# Project_Hail_Fally.net
KiCad netlist of a schematic drawn in EasyEDA Pro
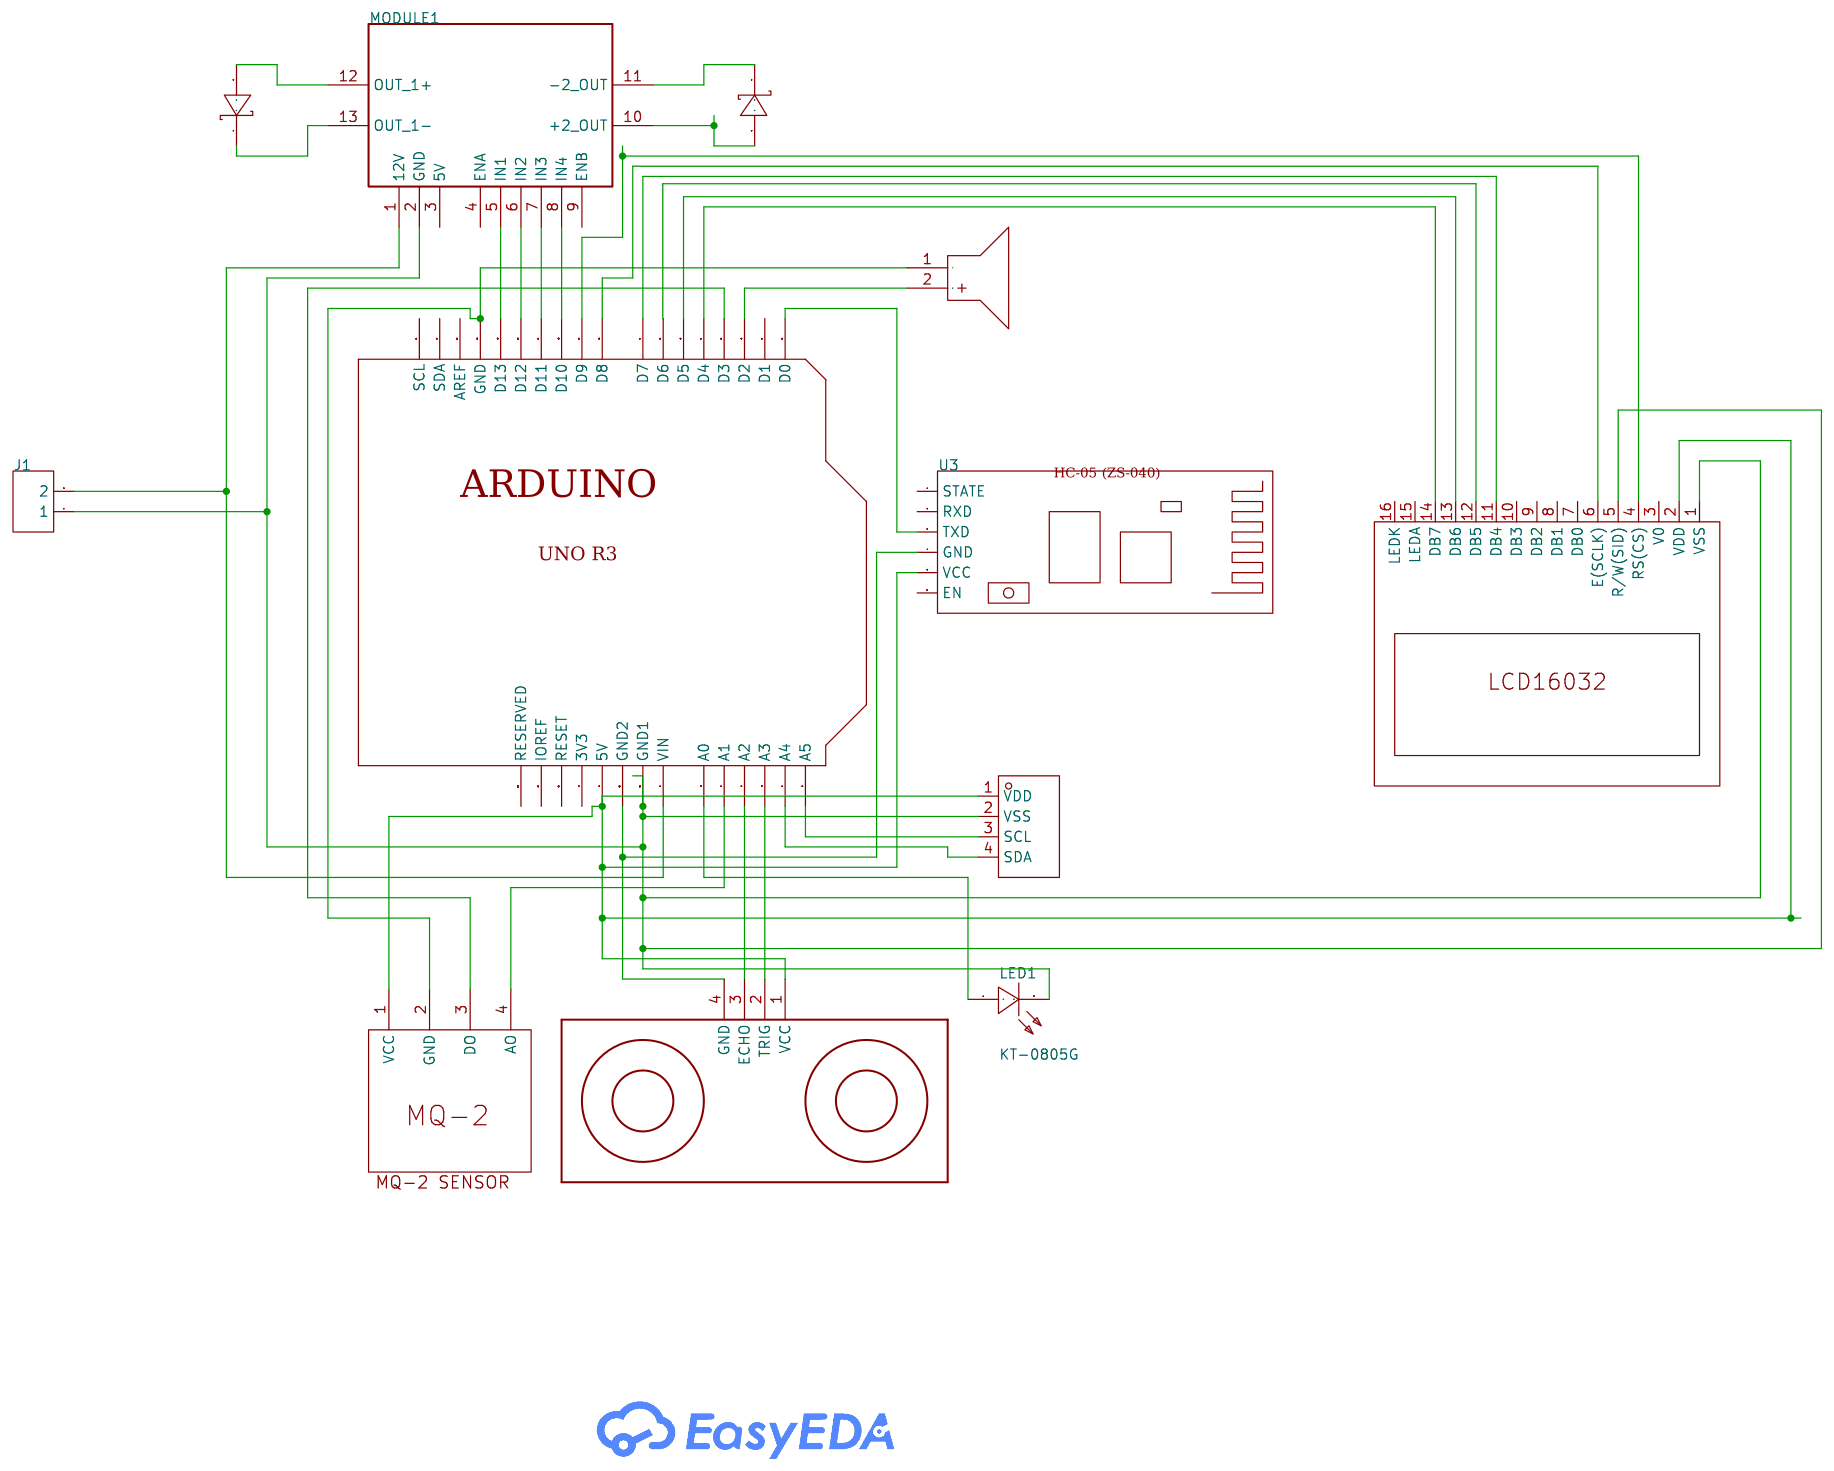
[diagram p0: schematic sheet]

(export (version "E")
  (design (tool "Eeschema 10.0.6"))
  (components
    (comp (ref "BUZZER1")
      (value "buzzer")
      (footprint "easyedapro:BUZ-TH_BD12.0-P6.00-D0.9-RD")
      (libsource (lib "easyedapro") (part "BUZZER"))
    )
    (comp (ref "D1")
      (value "1N5819WS")
      (footprint "easyedapro:SOD-323_L1.8-W1.3-LS2.5-RD")
      (fields (field (name "Manufacturer") "Hottech(合科泰)"))
      (libsource (lib "easyedapro") (part "1N5819WS"))
    )
    (comp (ref "D2")
      (value "1N5819WS")
      (footprint "easyedapro:SOD-323_L1.8-W1.3-LS2.5-RD")
      (fields (field (name "Manufacturer") "Hottech(合科泰)"))
      (libsource (lib "easyedapro") (part "1N5819WS"))
    )
    (comp (ref "J1")
      (value "Bettery Connector")
      (footprint "easyedapro:HDR-M-2.54_1X2")
      (libsource (lib "easyedapro") (part "Bettery Connector"))
    )
    (comp (ref "LED1")
      (value "KT-0805G")
      (footprint "easyedapro:LED0805-R-RD")
      (fields (field (name "Manufacturer") "KENTO"))
      (libsource (lib "easyedapro") (part "0805G (Green)"))
    )
    (comp (ref "MODULE1")
      (value "L298N DUAL H-BRIDGE MOTOR DRIVER MODULE COPY1")
      (footprint "easyedapro:L298N DUAL H-BRIDGE MOTOR DRIVER MODULE footprint")
      (libsource (lib "easyedapro") (part "L298N DUAL H-BRIDGE MOTOR DRIVER MODULE COPY1"))
    )
    (comp (ref "S1")
      (value "Sensor_MQ-2_module_vertical_AIH")
      (footprint "easyedapro:SENSOR_MQ-2_MODULE_VERTICAL_AIH")
      (libsource (lib "easyedapro") (part "MQ-2"))
    )
    (comp (ref "U$1")
      (value "Arduino Uno")
      (footprint "easyedapro:ARDUINO-R3")
      (libsource (lib "easyedapro") (part "Arduino Uno"))
    )
    (comp (ref "U1")
      (value "SMR16032-ZD")
      (footprint "easyedapro:LCD-TH_SMR16032-ZD")
      (libsource (lib "easyedapro") (part "SMR16032-ZD"))
    )
    (comp (ref "U2")
      (value "weklin_ultrasonic_ULTRASONIC-HC-SR04_")
      (footprint "easyedapro:ULTRASONIC-HC-SR04")
      (libsource (lib "easyedapro") (part "weklin_ultrasonic_ULTRASONIC-HC-SR04_"))
    )
    (comp (ref "U3")
      (value "HC05-Bluetooth-Module_AK")
      (footprint "easyedapro:hc05-bluetooth-module_ak")
      (description "Modulo bluetooth")
      (libsource (lib "easyedapro") (part "HC05-Bluetooth-Module_AK"))
    )
    (comp (ref "U4")
      (value "HIH7121-021-001S")
      (footprint "easyedapro:SIP-4_L4.9-W1.9-P1.27-L")
      (description "Voltage - Supply:2.3V~5.5V Voltage - Supply:2.3V~5.5V")
      (fields (field (name "Manufacturer") "Honeywell(霍尼韦尔)"))
      (libsource (lib "easyedapro") (part "HIH7121-021-001S"))
    )
  )
  (nets
    (net (code "1") (name "Net-(BUZZER1-+)") (class "Default")
      (node (ref "BUZZER1") (pin "2") (pinfunction "+_2") (pintype "input"))
      (node (ref "U$1") (pin "D2") (pinfunction "D2_D2") (pintype "bidirectional"))
    )
    (net (code "2") (name "Net-(BUZZER1--)") (class "Default")
      (node (ref "BUZZER1") (pin "1") (pinfunction "-_1") (pintype "input"))
      (node (ref "S1") (pin "2") (pinfunction "GND_2") (pintype "unspecified"))
      (node (ref "U$1") (pin "GND") (pinfunction "GND_GND") (pintype "bidirectional"))
    )
    (net (code "3") (name "Net-(D1-A)") (class "Default")
      (node (ref "D1") (pin "2") (pinfunction "A_2") (pintype "unspecified"))
      (node (ref "MODULE1") (pin "10") (pinfunction "+2_OUT_10") (pintype "output"))
    )
    (net (code "4") (name "Net-(D1-K)") (class "Default")
      (node (ref "D1") (pin "1") (pinfunction "K_1") (pintype "unspecified"))
      (node (ref "MODULE1") (pin "11") (pinfunction "-2_OUT_11") (pintype "output"))
    )
    (net (code "5") (name "Net-(D2-A)") (class "Default")
      (node (ref "D2") (pin "2") (pinfunction "A_2") (pintype "unspecified"))
      (node (ref "MODULE1") (pin "12") (pinfunction "OUT_1+_12") (pintype "output"))
    )
    (net (code "6") (name "Net-(D2-K)") (class "Default")
      (node (ref "D2") (pin "1") (pinfunction "K_1") (pintype "unspecified"))
      (node (ref "MODULE1") (pin "13") (pinfunction "OUT_1-_13") (pintype "output"))
    )
    (net (code "7") (name "Net-(LED1-A)") (class "Default")
      (node (ref "LED1") (pin "1") (pinfunction "A_1") (pintype "unspecified"))
      (node (ref "U$1") (pin "A0") (pinfunction "A0_A0") (pintype "bidirectional"))
    )
    (net (code "8") (name "Net-(LED1-K)") (class "Default")
      (node (ref "J1") (pin "1") (pinfunction "1_1") (pintype "unspecified"))
      (node (ref "LED1") (pin "2") (pinfunction "K_2") (pintype "unspecified"))
      (node (ref "MODULE1") (pin "2") (pinfunction "GND_2") (pintype "unspecified"))
      (node (ref "U$1") (pin "GND1") (pinfunction "GND1_GND1") (pintype "bidirectional"))
      (node (ref "U1") (pin "1") (pinfunction "VSS_1") (pintype "unspecified"))
      (node (ref "U1") (pin "5") (pinfunction "R/W(SID)_5") (pintype "unspecified"))
      (node (ref "U4") (pin "2") (pinfunction "VSS_2") (pintype "unspecified"))
    )
    (net (code "9") (name "Net-(MODULE1-12V)") (class "Default")
      (node (ref "J1") (pin "2") (pinfunction "2_2") (pintype "unspecified"))
      (node (ref "MODULE1") (pin "1") (pinfunction "12V_1") (pintype "unspecified"))
      (node (ref "U$1") (pin "VIN") (pinfunction "VIN_VIN") (pintype "bidirectional"))
    )
    (net (code "10") (name "Net-(MODULE1-IN1)") (class "Default")
      (node (ref "MODULE1") (pin "5") (pinfunction "IN1_5") (pintype "input"))
      (node (ref "U$1") (pin "D13") (pinfunction "D13_D13") (pintype "bidirectional"))
    )
    (net (code "11") (name "Net-(MODULE1-IN2)") (class "Default")
      (node (ref "MODULE1") (pin "6") (pinfunction "IN2_6") (pintype "input"))
      (node (ref "U$1") (pin "D12") (pinfunction "D12_D12") (pintype "bidirectional"))
    )
    (net (code "12") (name "Net-(MODULE1-IN3)") (class "Default")
      (node (ref "MODULE1") (pin "7") (pinfunction "IN3_7") (pintype "input"))
      (node (ref "U$1") (pin "D11") (pinfunction "D11_D11") (pintype "bidirectional"))
    )
    (net (code "13") (name "Net-(MODULE1-IN4)") (class "Default")
      (node (ref "MODULE1") (pin "8") (pinfunction "IN4_8") (pintype "input"))
      (node (ref "U$1") (pin "D10") (pinfunction "D10_D10") (pintype "bidirectional"))
    )
    (net (code "14") (name "Net-(S1-AO)") (class "Default")
      (node (ref "S1") (pin "4") (pinfunction "AO_4") (pintype "unspecified"))
      (node (ref "U$1") (pin "A1") (pinfunction "A1_A1") (pintype "bidirectional"))
    )
    (net (code "15") (name "Net-(S1-DO)") (class "Default")
      (node (ref "S1") (pin "3") (pinfunction "DO_3") (pintype "unspecified"))
      (node (ref "U$1") (pin "D3") (pinfunction "D3_D3") (pintype "bidirectional"))
    )
    (net (code "16") (name "Net-(S1-VCC)") (class "Default")
      (node (ref "S1") (pin "1") (pinfunction "VCC_1") (pintype "unspecified"))
      (node (ref "U$1") (pin "5V") (pinfunction "5V_5V") (pintype "bidirectional"))
      (node (ref "U1") (pin "2") (pinfunction "VDD_2") (pintype "unspecified"))
      (node (ref "U2") (pin "1") (pinfunction "VCC_1") (pintype "unspecified"))
      (node (ref "U3") (pin "5") (pinfunction "VCC_5") (pintype "output"))
      (node (ref "U4") (pin "1") (pinfunction "VDD_1") (pintype "unspecified"))
    )
    (net (code "17") (name "Net-(U1-DB4)") (class "Default")
      (node (ref "U$1") (pin "D7") (pinfunction "D7_D7") (pintype "bidirectional"))
      (node (ref "U1") (pin "11") (pinfunction "DB4_11") (pintype "unspecified"))
    )
    (net (code "18") (name "Net-(U1-DB6)") (class "Default")
      (node (ref "U$1") (pin "D5") (pinfunction "D5_D5") (pintype "bidirectional"))
      (node (ref "U1") (pin "13") (pinfunction "DB6_13") (pintype "unspecified"))
    )
    (net (code "19") (name "Net-(U1-DB7)") (class "Default")
      (node (ref "U$1") (pin "D4") (pinfunction "D4_D4") (pintype "bidirectional"))
      (node (ref "U1") (pin "14") (pinfunction "DB7_14") (pintype "unspecified"))
    )
    (net (code "20") (name "Net-(U1-E(SCLK))") (class "Default")
      (node (ref "U$1") (pin "D8") (pinfunction "D8_D8") (pintype "bidirectional"))
      (node (ref "U1") (pin "6") (pinfunction "E(SCLK)_6") (pintype "unspecified"))
    )
    (net (code "21") (name "Net-(U1-RS(CS))") (class "Default")
      (node (ref "U$1") (pin "D9") (pinfunction "D9_D9") (pintype "bidirectional"))
      (node (ref "U1") (pin "4") (pinfunction "RS(CS)_4") (pintype "unspecified"))
    )
    (net (code "22") (name "Net-(U2-ECHO)") (class "Default")
      (node (ref "U$1") (pin "A2") (pinfunction "A2_A2") (pintype "bidirectional"))
      (node (ref "U2") (pin "3") (pinfunction "ECHO_3") (pintype "output"))
    )
    (net (code "23") (name "Net-(U2-GND)") (class "Default")
      (node (ref "U$1") (pin "GND2") (pinfunction "GND2_GND2") (pintype "bidirectional"))
      (node (ref "U2") (pin "4") (pinfunction "GND_4") (pintype "unspecified"))
      (node (ref "U3") (pin "4") (pinfunction "GND_4") (pintype "input"))
    )
    (net (code "24") (name "Net-(U2-TRIG)") (class "Default")
      (node (ref "U$1") (pin "A3") (pinfunction "A3_A3") (pintype "bidirectional"))
      (node (ref "U2") (pin "2") (pinfunction "TRIG_2") (pintype "input"))
    )
    (net (code "25") (name "Net-(U3-TXD)") (class "Default")
      (node (ref "U$1") (pin "D0") (pinfunction "D0_D0") (pintype "bidirectional"))
      (node (ref "U3") (pin "3") (pinfunction "TXD_3") (pintype "input"))
    )
    (net (code "26") (name "Net-(U4-SCL)") (class "Default")
      (node (ref "U$1") (pin "A5") (pinfunction "A5_A5") (pintype "bidirectional"))
      (node (ref "U4") (pin "3") (pinfunction "SCL_3") (pintype "unspecified"))
    )
    (net (code "27") (name "Net-(U4-SDA)") (class "Default")
      (node (ref "U$1") (pin "A4") (pinfunction "A4_A4") (pintype "bidirectional"))
      (node (ref "U4") (pin "4") (pinfunction "SDA_4") (pintype "unspecified"))
    )
    (net (code "28") (name "unconnected-(MODULE1-5V-Pad3)") (class "Default")
      (node (ref "MODULE1") (pin "3") (pinfunction "5V_3") (pintype "unspecified"))
    )
    (net (code "29") (name "unconnected-(MODULE1-ENA-Pad4)") (class "Default")
      (node (ref "MODULE1") (pin "4") (pinfunction "ENA_4") (pintype "input"))
    )
    (net (code "30") (name "unconnected-(MODULE1-ENB-Pad9)") (class "Default")
      (node (ref "MODULE1") (pin "9") (pinfunction "ENB_9") (pintype "input"))
    )
    (net (code "31") (name "unconnected-(U$1-3V3-Pad3V)") (class "Default")
      (node (ref "U$1") (pin "3V") (pinfunction "3V3_3V") (pintype "bidirectional"))
    )
    (net (code "32") (name "unconnected-(U$1-PadAREF)") (class "Default")
      (node (ref "U$1") (pin "AREF") (pinfunction "AREF_AREF") (pintype "bidirectional"))
    )
    (net (code "33") (name "unconnected-(U$1-PadD1)") (class "Default")
      (node (ref "U$1") (pin "D1") (pinfunction "D1_D1") (pintype "bidirectional"))
    )
    (net (code "34") (name "unconnected-(U$1-PadD6)") (class "Default")
      (node (ref "U$1") (pin "D6") (pinfunction "D6_D6") (pintype "bidirectional"))
    )
    (net (code "35") (name "unconnected-(U$1-PadIOREF)") (class "Default")
      (node (ref "U$1") (pin "IOREF") (pinfunction "IOREF_IOREF") (pintype "bidirectional"))
    )
    (net (code "36") (name "unconnected-(U$1-PadRESERVED)") (class "Default")
      (node (ref "U$1") (pin "RESERVED") (pinfunction "RESERVED_RESERVED") (pintype "bidirectional"))
    )
    (net (code "37") (name "unconnected-(U$1-PadRESET)") (class "Default")
      (node (ref "U$1") (pin "RESET") (pinfunction "RESET_RESET") (pintype "bidirectional"))
    )
    (net (code "38") (name "unconnected-(U$1-PadSCL)") (class "Default")
      (node (ref "U$1") (pin "SCL") (pinfunction "SCL_SCL") (pintype "bidirectional"))
    )
    (net (code "39") (name "unconnected-(U$1-PadSDA)") (class "Default")
      (node (ref "U$1") (pin "SDA") (pinfunction "SDA_SDA") (pintype "bidirectional"))
    )
    (net (code "40") (name "unconnected-(U1-DB0-Pad7)") (class "Default")
      (node (ref "U1") (pin "7") (pinfunction "DB0_7") (pintype "unspecified"))
    )
    (net (code "41") (name "unconnected-(U1-DB1-Pad8)") (class "Default")
      (node (ref "U1") (pin "8") (pinfunction "DB1_8") (pintype "unspecified"))
    )
    (net (code "42") (name "unconnected-(U1-DB2-Pad9)") (class "Default")
      (node (ref "U1") (pin "9") (pinfunction "DB2_9") (pintype "unspecified"))
    )
    (net (code "43") (name "unconnected-(U1-DB3-Pad10)") (class "Default")
      (node (ref "U1") (pin "10") (pinfunction "DB3_10") (pintype "unspecified"))
    )
    (net (code "44") (name "unconnected-(U1-DB5-Pad12)") (class "Default")
      (node (ref "U1") (pin "12") (pinfunction "DB5_12") (pintype "unspecified"))
    )
    (net (code "45") (name "unconnected-(U1-LEDA-Pad15)") (class "Default")
      (node (ref "U1") (pin "15") (pinfunction "LEDA_15") (pintype "unspecified"))
    )
    (net (code "46") (name "unconnected-(U1-LEDK-Pad16)") (class "Default")
      (node (ref "U1") (pin "16") (pinfunction "LEDK_16") (pintype "unspecified"))
    )
    (net (code "47") (name "unconnected-(U1-V0-Pad3)") (class "Default")
      (node (ref "U1") (pin "3") (pinfunction "V0_3") (pintype "unspecified"))
    )
    (net (code "48") (name "unconnected-(U3-EN-Pad6)") (class "Default")
      (node (ref "U3") (pin "6") (pinfunction "EN_6") (pintype "bidirectional"))
    )
    (net (code "49") (name "unconnected-(U3-RXD-Pad2)") (class "Default")
      (node (ref "U3") (pin "2") (pinfunction "RXD_2") (pintype "input"))
    )
    (net (code "50") (name "unconnected-(U3-STATE-Pad1)") (class "Default")
      (node (ref "U3") (pin "1") (pinfunction "STATE_1") (pintype "input"))
    )
  )
)
